# CPU.net
KiCad netlist of a schematic drawn in Altium Designer
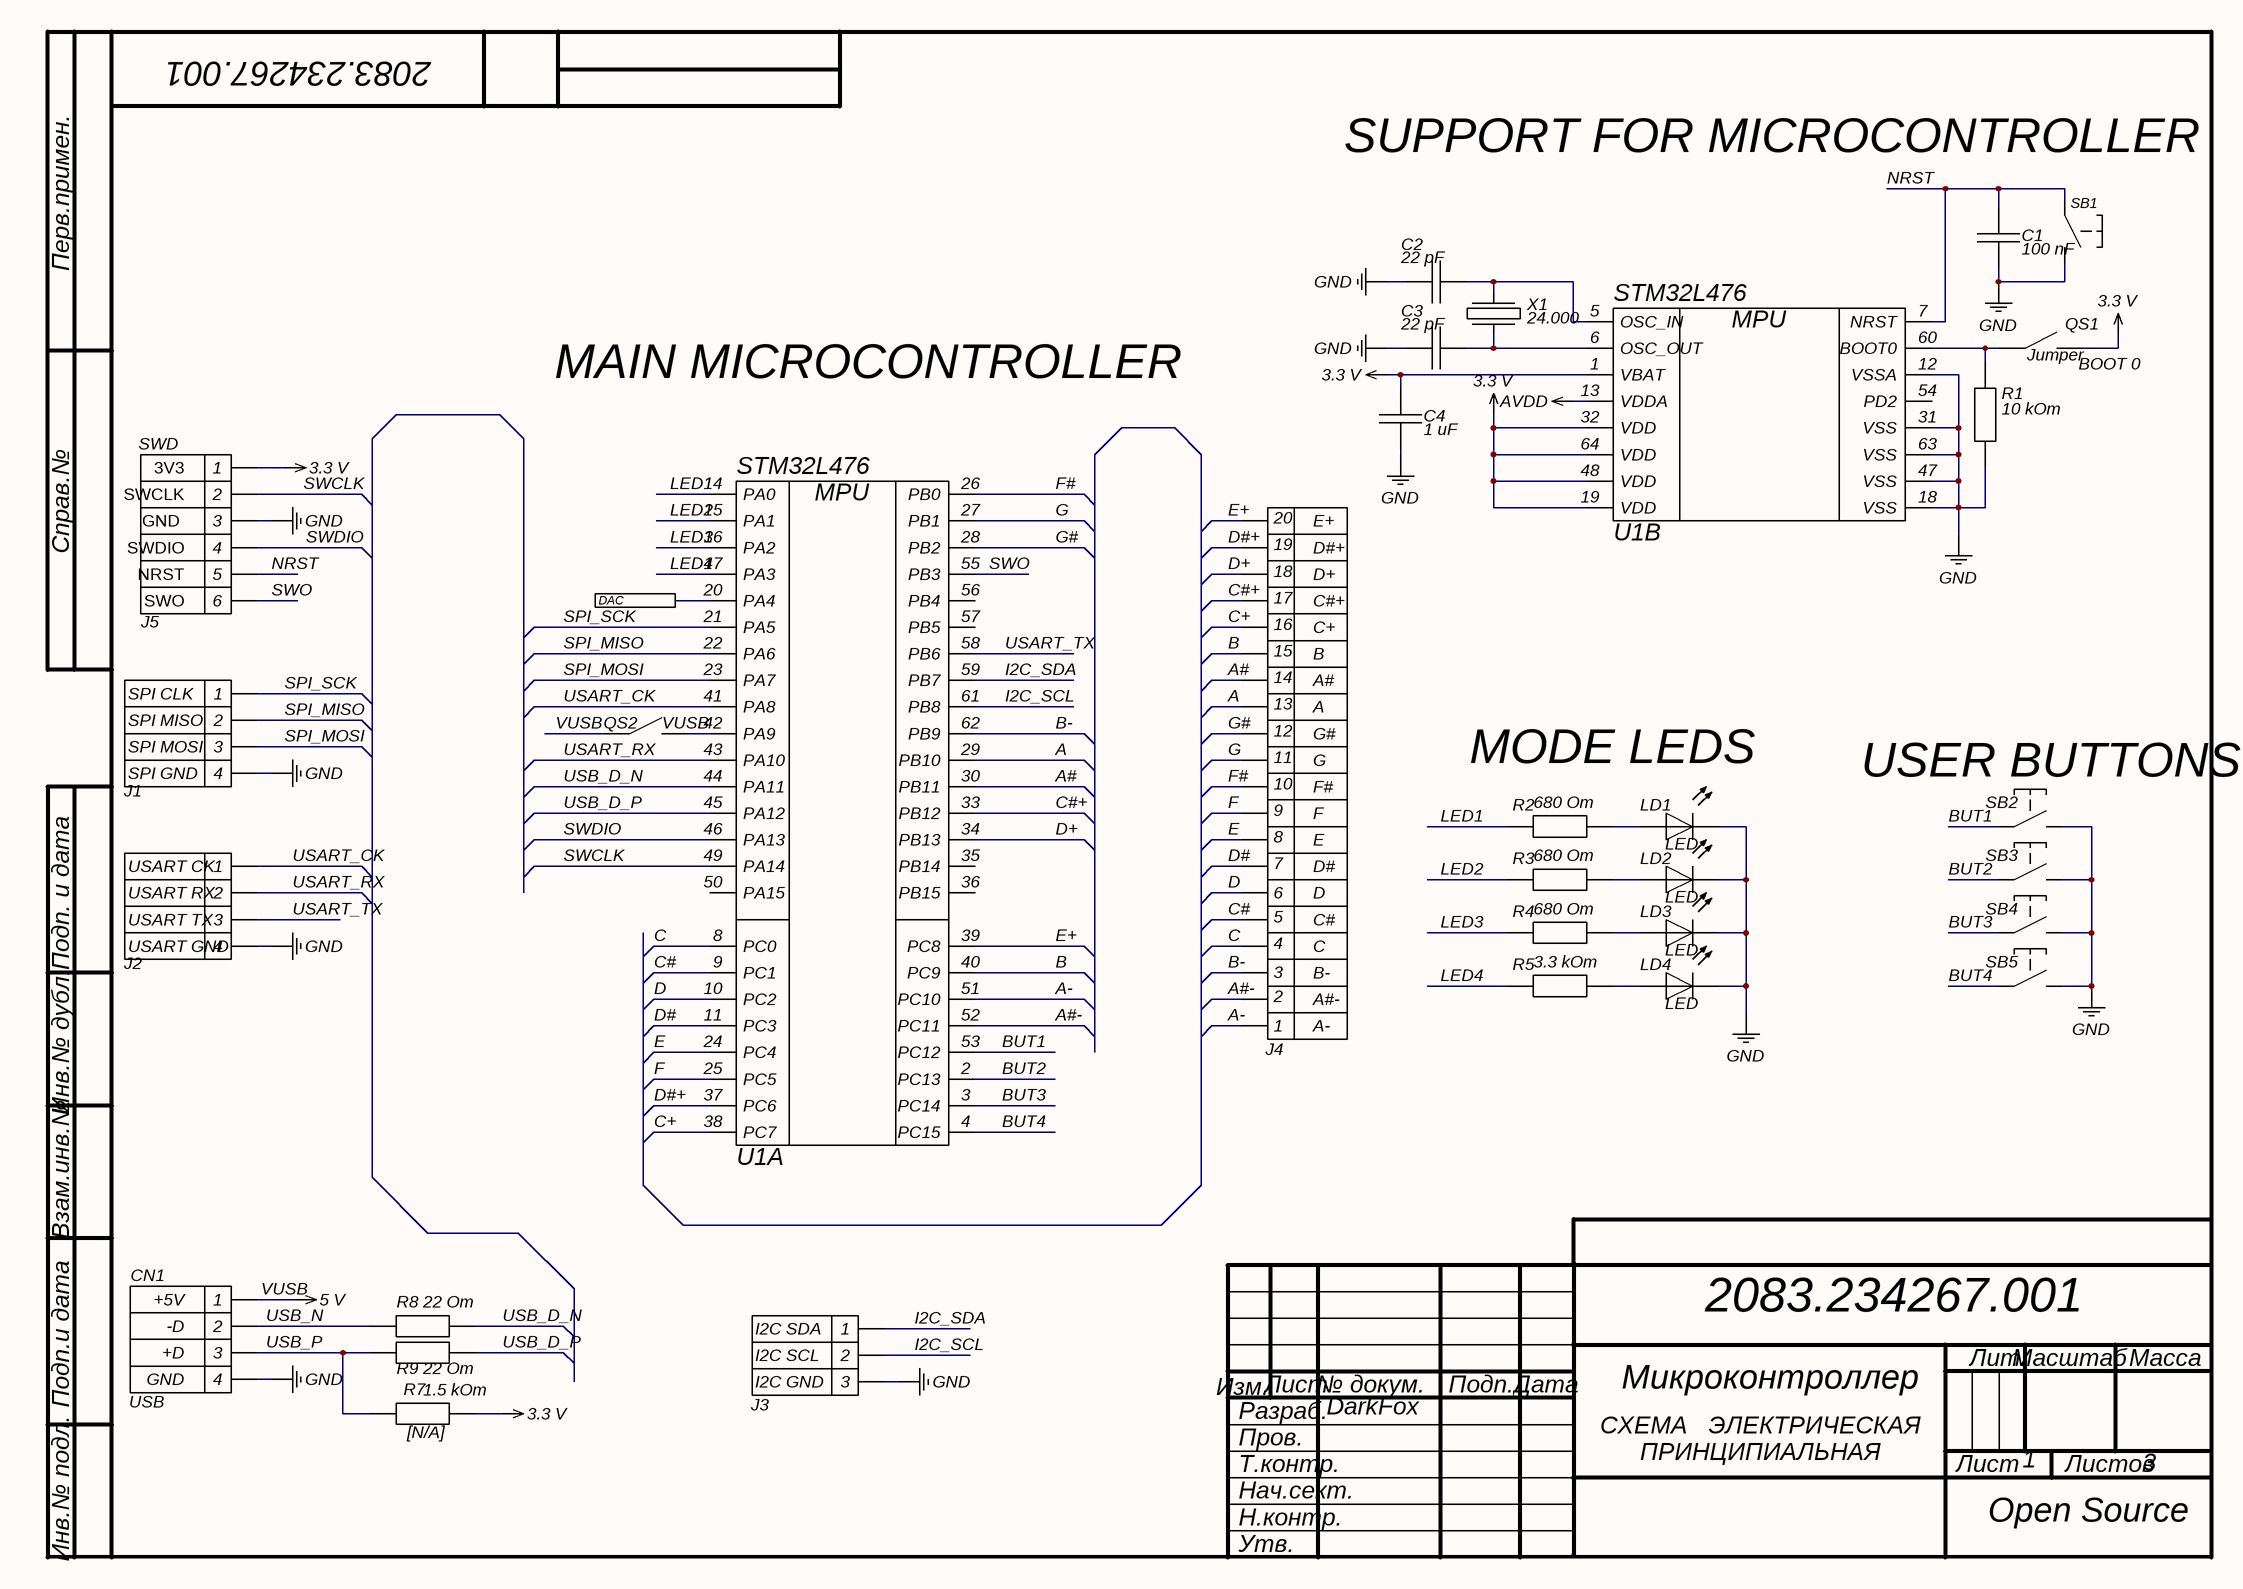
[diagram p0: CPU.SchDoc]

(export (version "E")
  (design (tool "Eeschema 10.0.6"))
  (components
    (comp (ref "C1") (value "100 nF") (footprint "0603") (libsource (lib "MyLib") (part "Cup")))
    (comp (ref "C2") (value "22 pF") (footprint "0805") (libsource (lib "MyLib") (part "Cup")))
    (comp (ref "C3") (value "22 pF") (footprint "0805") (libsource (lib "MyLib") (part "Cup")))
    (comp (ref "C4") (value "1 uF") (footprint "0603") (libsource (lib "MyLib") (part "Cup")))
    (comp (ref "CN1") (value "USB") (footprint "USB") (libsource (lib "ECard_Lib") (part "USB_2")))
    (comp (ref "J1") (value "4x2.54") (footprint "SMD 4x2.54") (libsource (lib "ECard_Lib") (part "4x2.54")))
    (comp (ref "J2") (value "4x2.54") (footprint "SMD 4x2.54") (libsource (lib "ECard_Lib") (part "4x2.54")))
    (comp (ref "J3") (value "3x2.54") (footprint "SMD 3x2.54") (libsource (lib "ECard_Lib") (part "3x2.54")))
    (comp (ref "J4")
      (value "piano_full")
      (footprint "PIANO_FULL")
      (libsource (lib "ECard_Lib") (part "piano_full"))
    )
    (comp (ref "J5") (value "SWD") (footprint "SWD_6_2.54") (libsource (lib "ECard_Lib") (part "SWD")))
    (comp (ref "LD1") (value "LED") (footprint "0805") (libsource (lib "MyLib") (part "LED")))
    (comp (ref "LD2") (value "LED") (footprint "0805") (libsource (lib "MyLib") (part "LED")))
    (comp (ref "LD3") (value "LED") (footprint "0805") (libsource (lib "MyLib") (part "LED")))
    (comp (ref "LD4") (value "LED") (footprint "0805") (libsource (lib "MyLib") (part "LED")))
    (comp (ref "QS1") (value "Jumper") (footprint "SB") (libsource (lib "ECard_Lib") (part "Jumper")))
    (comp (ref "QS2") (value "Jumper") (footprint "SB") (libsource (lib "ECard_Lib") (part "Jumper")))
    (comp (ref "R1") (value "10 kOm") (footprint "0603") (libsource (lib "ECard_Lib") (part "Res")))
    (comp (ref "R2") (value "680 Om") (footprint "1206") (libsource (lib "MyLib") (part "Res")))
    (comp (ref "R3") (value "680 Om") (footprint "1206") (libsource (lib "MyLib") (part "Res")))
    (comp (ref "R4") (value "680 Om") (footprint "1206") (libsource (lib "MyLib") (part "Res")))
    (comp (ref "R5") (value "3.3 kOm") (footprint "1206") (libsource (lib "MyLib") (part "Res")))
    (comp (ref "R7") (value "1.5 kOm") (footprint "1206") (libsource (lib "MyLib") (part "Res")))
    (comp (ref "R8") (value "22 Om") (footprint "1206") (libsource (lib "MyLib") (part "Res")))
    (comp (ref "R9") (value "22 Om") (footprint "1206") (libsource (lib "MyLib") (part "Res")))
    (comp (ref "SB1") (value "but") (footprint "TS44-SMD") (libsource (lib "ECard_Lib") (part "but")))
    (comp (ref "SB2") (value "but") (footprint "TS44-SMD") (libsource (lib "ECard_Lib") (part "but")))
    (comp (ref "SB3") (value "but") (footprint "TS44-SMD") (libsource (lib "ECard_Lib") (part "but")))
    (comp (ref "SB4") (value "but") (footprint "TS44-SMD") (libsource (lib "ECard_Lib") (part "but")))
    (comp (ref "SB5") (value "but") (footprint "TS44-SMD") (libsource (lib "ECard_Lib") (part "but")))
    (comp (ref "U1")
      (value "STM32L476")
      (footprint "LQFP - 64")
      (libsource (lib "ECard_Lib") (part "STM32L476RG"))
    )
    (comp (ref "X1")
      (value "24.000")
      (footprint "CSX-3225")
      (description "Crystal Resonator")
      (libsource (lib "MyLib") (part "CSX-3225"))
    )
  )
  (nets
    (net (code "1") (name "/A") (class "Default")
      (node (ref "J4") (pin "13") (pinfunction "A_13") (pintype "passive"))
      (node (ref "U1") (pin "29") (pinfunction "PB10_29") (pintype "passive"))
    )
    (net (code "2") (name "/A#") (class "Default")
      (node (ref "J4") (pin "14") (pinfunction "A#_14") (pintype "passive"))
      (node (ref "U1") (pin "30") (pinfunction "PB11_30") (pintype "passive"))
    )
    (net (code "3") (name "/A#-") (class "Default")
      (node (ref "J4") (pin "2") (pinfunction "A#-_2") (pintype "passive"))
      (node (ref "U1") (pin "52") (pinfunction "PC11_52") (pintype "passive"))
    )
    (net (code "4") (name "/A-") (class "Default")
      (node (ref "J4") (pin "1") (pinfunction "A-_1") (pintype "passive"))
      (node (ref "U1") (pin "51") (pinfunction "PC10_51") (pintype "passive"))
    )
    (net (code "5") (name "/B") (class "Default")
      (node (ref "J4") (pin "15") (pinfunction "B_15") (pintype "passive"))
      (node (ref "U1") (pin "40") (pinfunction "PC9_40") (pintype "passive"))
    )
    (net (code "6") (name "/B-") (class "Default")
      (node (ref "J4") (pin "3") (pinfunction "B-_3") (pintype "passive"))
      (node (ref "U1") (pin "62") (pinfunction "PB9_62") (pintype "passive"))
    )
    (net (code "7") (name "/BUT1") (class "Default")
      (node (ref "SB2") (pin "1") (pinfunction "1_1") (pintype "passive"))
      (node (ref "U1") (pin "53") (pinfunction "PC12_53") (pintype "passive"))
    )
    (net (code "8") (name "/BUT2") (class "Default")
      (node (ref "SB3") (pin "1") (pinfunction "1_1") (pintype "passive"))
      (node (ref "U1") (pin "2") (pinfunction "PC13_2") (pintype "passive"))
    )
    (net (code "9") (name "/BUT3") (class "Default")
      (node (ref "SB4") (pin "1") (pinfunction "1_1") (pintype "passive"))
      (node (ref "U1") (pin "3") (pinfunction "PC14_3") (pintype "passive"))
    )
    (net (code "10") (name "/BUT4") (class "Default")
      (node (ref "SB5") (pin "1") (pinfunction "1_1") (pintype "passive"))
      (node (ref "U1") (pin "4") (pinfunction "PC15_4") (pintype "passive"))
    )
    (net (code "11") (name "/C") (class "Default")
      (node (ref "J4") (pin "4") (pinfunction "C_4") (pintype "passive"))
      (node (ref "U1") (pin "8") (pinfunction "PC0_8") (pintype "passive"))
    )
    (net (code "12") (name "/C#") (class "Default")
      (node (ref "J4") (pin "5") (pinfunction "C#_5") (pintype "passive"))
      (node (ref "U1") (pin "9") (pinfunction "PC1_9") (pintype "passive"))
    )
    (net (code "13") (name "/C#+") (class "Default")
      (node (ref "J4") (pin "17") (pinfunction "C#+_17") (pintype "passive"))
      (node (ref "U1") (pin "33") (pinfunction "PB12_33") (pintype "passive"))
    )
    (net (code "14") (name "/C+") (class "Default")
      (node (ref "J4") (pin "16") (pinfunction "C+_16") (pintype "passive"))
      (node (ref "U1") (pin "38") (pinfunction "PC7_38") (pintype "passive"))
    )
    (net (code "15") (name "/D") (class "Default")
      (node (ref "J4") (pin "6") (pinfunction "D_6") (pintype "passive"))
      (node (ref "U1") (pin "10") (pinfunction "PC2_10") (pintype "passive"))
    )
    (net (code "16") (name "/D#") (class "Default")
      (node (ref "J4") (pin "7") (pinfunction "D#_7") (pintype "passive"))
      (node (ref "U1") (pin "11") (pinfunction "PC3_11") (pintype "passive"))
    )
    (net (code "17") (name "/D#+") (class "Default")
      (node (ref "J4") (pin "19") (pinfunction "D#+_19") (pintype "passive"))
      (node (ref "U1") (pin "37") (pinfunction "PC6_37") (pintype "passive"))
    )
    (net (code "18") (name "/D+") (class "Default")
      (node (ref "J4") (pin "18") (pinfunction "D+_18") (pintype "passive"))
      (node (ref "U1") (pin "34") (pinfunction "PB13_34") (pintype "passive"))
    )
    (net (code "19") (name "/DAC") (class "Default")
      (node (ref "U1") (pin "20") (pinfunction "PA4_20") (pintype "passive"))
    )
    (net (code "20") (name "/E") (class "Default")
      (node (ref "J4") (pin "8") (pinfunction "E_8") (pintype "passive"))
      (node (ref "U1") (pin "24") (pinfunction "PC4_24") (pintype "passive"))
    )
    (net (code "21") (name "/E+") (class "Default")
      (node (ref "J4") (pin "20") (pinfunction "E+_20") (pintype "passive"))
      (node (ref "U1") (pin "39") (pinfunction "PC8_39") (pintype "passive"))
    )
    (net (code "22") (name "/F") (class "Default")
      (node (ref "J4") (pin "9") (pinfunction "F_9") (pintype "passive"))
      (node (ref "U1") (pin "25") (pinfunction "PC5_25") (pintype "passive"))
    )
    (net (code "23") (name "/F#") (class "Default")
      (node (ref "J4") (pin "10") (pinfunction "F#_10") (pintype "passive"))
      (node (ref "U1") (pin "26") (pinfunction "PB0_26") (pintype "passive"))
    )
    (net (code "24") (name "/G") (class "Default")
      (node (ref "J4") (pin "11") (pinfunction "G_11") (pintype "passive"))
      (node (ref "U1") (pin "27") (pinfunction "PB1_27") (pintype "passive"))
    )
    (net (code "25") (name "/G#") (class "Default")
      (node (ref "J4") (pin "12") (pinfunction "G#_12") (pintype "passive"))
      (node (ref "U1") (pin "28") (pinfunction "PB2_28") (pintype "passive"))
    )
    (net (code "26") (name "/I2C_SCL") (class "Default")
      (node (ref "J3") (pin "2") (pinfunction "2_2") (pintype "passive"))
      (node (ref "U1") (pin "61") (pinfunction "PB8_61") (pintype "passive"))
    )
    (net (code "27") (name "/I2C_SDA") (class "Default")
      (node (ref "J3") (pin "1") (pinfunction "1_1") (pintype "passive"))
      (node (ref "U1") (pin "59") (pinfunction "PB7_59") (pintype "passive"))
    )
    (net (code "28") (name "/LED1") (class "Default")
      (node (ref "R2") (pin "1") (pinfunction "1_1") (pintype "passive"))
      (node (ref "U1") (pin "14") (pinfunction "PA0_14") (pintype "passive"))
    )
    (net (code "29") (name "/LED2") (class "Default")
      (node (ref "R3") (pin "1") (pinfunction "1_1") (pintype "passive"))
      (node (ref "U1") (pin "15") (pinfunction "PA1_15") (pintype "passive"))
    )
    (net (code "30") (name "/LED3") (class "Default")
      (node (ref "R4") (pin "1") (pinfunction "1_1") (pintype "passive"))
      (node (ref "U1") (pin "16") (pinfunction "PA2_16") (pintype "passive"))
    )
    (net (code "31") (name "/LED4") (class "Default")
      (node (ref "R5") (pin "1") (pinfunction "1_1") (pintype "passive"))
      (node (ref "U1") (pin "17") (pinfunction "PA3_17") (pintype "passive"))
    )
    (net (code "32") (name "/NRST") (class "Default")
      (node (ref "C1") (pin "2") (pinfunction "2_2") (pintype "passive"))
      (node (ref "J5") (pin "5") (pinfunction "NRST_5") (pintype "passive"))
      (node (ref "SB1") (pin "1") (pinfunction "1_1") (pintype "passive"))
      (node (ref "U1") (pin "7") (pinfunction "NRST_7") (pintype "passive"))
    )
    (net (code "33") (name "/SPI_MISO") (class "Default")
      (node (ref "J1") (pin "2") (pinfunction "2_2") (pintype "passive"))
      (node (ref "U1") (pin "22") (pinfunction "PA6_22") (pintype "passive"))
    )
    (net (code "34") (name "/SPI_MOSI") (class "Default")
      (node (ref "J1") (pin "3") (pinfunction "3_3") (pintype "passive"))
      (node (ref "U1") (pin "23") (pinfunction "PA7_23") (pintype "passive"))
    )
    (net (code "35") (name "/SPI_SCK") (class "Default")
      (node (ref "J1") (pin "1") (pinfunction "1_1") (pintype "passive"))
      (node (ref "U1") (pin "21") (pinfunction "PA5_21") (pintype "passive"))
    )
    (net (code "36") (name "/SWCLK") (class "Default")
      (node (ref "J5") (pin "2") (pinfunction "SWCLK_2") (pintype "passive"))
      (node (ref "U1") (pin "49") (pinfunction "PA14_49") (pintype "passive"))
    )
    (net (code "37") (name "/SWDIO") (class "Default")
      (node (ref "J5") (pin "4") (pinfunction "SWDIO_4") (pintype "passive"))
      (node (ref "U1") (pin "46") (pinfunction "PA13_46") (pintype "passive"))
    )
    (net (code "38") (name "/SWO") (class "Default")
      (node (ref "J5") (pin "6") (pinfunction "SWO_6") (pintype "passive"))
      (node (ref "U1") (pin "55") (pinfunction "PB3_55") (pintype "passive"))
    )
    (net (code "39") (name "/USART_CK") (class "Default")
      (node (ref "J2") (pin "1") (pinfunction "1_1") (pintype "passive"))
      (node (ref "U1") (pin "41") (pinfunction "PA8_41") (pintype "passive"))
    )
    (net (code "40") (name "/USART_RX") (class "Default")
      (node (ref "J2") (pin "2") (pinfunction "2_2") (pintype "passive"))
      (node (ref "U1") (pin "43") (pinfunction "PA10_43") (pintype "passive"))
    )
    (net (code "41") (name "/USART_TX") (class "Default")
      (node (ref "J2") (pin "3") (pinfunction "3_3") (pintype "passive"))
      (node (ref "U1") (pin "58") (pinfunction "PB6_58") (pintype "passive"))
    )
    (net (code "42") (name "/USB_D_N") (class "Default")
      (node (ref "R8") (pin "2") (pinfunction "2_2") (pintype "passive"))
      (node (ref "U1") (pin "44") (pinfunction "PA11_44") (pintype "passive"))
    )
    (net (code "43") (name "/USB_D_P") (class "Default")
      (node (ref "R9") (pin "2") (pinfunction "2_2") (pintype "passive"))
      (node (ref "U1") (pin "45") (pinfunction "PA12_45") (pintype "passive"))
    )
    (net (code "44") (name "/USB_N") (class "Default")
      (node (ref "CN1") (pin "2") (pinfunction "-D_2") (pintype "passive"))
      (node (ref "R8") (pin "1") (pinfunction "1_1") (pintype "passive"))
    )
    (net (code "45") (name "/USB_P") (class "Default")
      (node (ref "CN1") (pin "3") (pinfunction "+D_3") (pintype "passive"))
      (node (ref "R7") (pin "1") (pinfunction "1_1") (pintype "passive"))
      (node (ref "R9") (pin "1") (pinfunction "1_1") (pintype "passive"))
    )
    (net (code "46") (name "3.3 V") (class "Default")
      (node (ref "C4") (pin "2") (pinfunction "2_2") (pintype "passive"))
      (node (ref "J5") (pin "1") (pinfunction "3V3_1") (pintype "passive"))
      (node (ref "QS1") (pin "2") (pinfunction "2_2") (pintype "passive"))
      (node (ref "R7") (pin "2") (pinfunction "2_2") (pintype "passive"))
      (node (ref "U1") (pin "1") (pinfunction "VBAT_1") (pintype "passive"))
      (node (ref "U1") (pin "19") (pinfunction "VDD_19") (pintype "passive"))
      (node (ref "U1") (pin "32") (pinfunction "VDD_32") (pintype "passive"))
      (node (ref "U1") (pin "48") (pinfunction "VDD_48") (pintype "passive"))
      (node (ref "U1") (pin "64") (pinfunction "VDD_64") (pintype "passive"))
    )
    (net (code "47") (name "5 V") (class "Default")
      (node (ref "CN1") (pin "1") (pinfunction "+5V_1") (pintype "power_in"))
      (node (ref "QS2") (pin "1") (pinfunction "1_1") (pintype "passive"))
    )
    (net (code "48") (name "AVDD") (class "Default")
      (node (ref "U1") (pin "13") (pinfunction "VDDA_13") (pintype "passive"))
    )
    (net (code "49") (name "GND") (class "Default")
      (node (ref "C1") (pin "1") (pinfunction "1_1") (pintype "passive"))
      (node (ref "C2") (pin "1") (pinfunction "1_1") (pintype "passive"))
      (node (ref "C3") (pin "1") (pinfunction "1_1") (pintype "passive"))
      (node (ref "C4") (pin "1") (pinfunction "1_1") (pintype "passive"))
      (node (ref "CN1") (pin "4") (pinfunction "GND_4") (pintype "passive"))
      (node (ref "J1") (pin "4") (pinfunction "4_4") (pintype "passive"))
      (node (ref "J2") (pin "4") (pinfunction "4_4") (pintype "passive"))
      (node (ref "J3") (pin "3") (pinfunction "3_3") (pintype "passive"))
      (node (ref "J5") (pin "3") (pinfunction "GND_3") (pintype "passive"))
      (node (ref "LD1") (pin "2") (pinfunction "2_2") (pintype "passive"))
      (node (ref "LD2") (pin "2") (pinfunction "2_2") (pintype "passive"))
      (node (ref "LD3") (pin "2") (pinfunction "2_2") (pintype "passive"))
      (node (ref "LD4") (pin "2") (pinfunction "2_2") (pintype "passive"))
      (node (ref "R1") (pin "1") (pinfunction "1_1") (pintype "passive"))
      (node (ref "SB1") (pin "2") (pinfunction "2_2") (pintype "passive"))
      (node (ref "SB2") (pin "2") (pinfunction "2_2") (pintype "passive"))
      (node (ref "SB3") (pin "2") (pinfunction "2_2") (pintype "passive"))
      (node (ref "SB4") (pin "2") (pinfunction "2_2") (pintype "passive"))
      (node (ref "SB5") (pin "2") (pinfunction "2_2") (pintype "passive"))
      (node (ref "U1") (pin "12") (pinfunction "VSSA_12") (pintype "passive"))
      (node (ref "U1") (pin "18") (pinfunction "VSS_18") (pintype "passive"))
      (node (ref "U1") (pin "31") (pinfunction "VSS_31") (pintype "passive"))
      (node (ref "U1") (pin "47") (pinfunction "VSS_47") (pintype "passive"))
      (node (ref "U1") (pin "63") (pinfunction "VSS_63") (pintype "passive"))
    )
    (net (code "50") (name "Net-(LD1-2-Pad1)") (class "Default")
      (node (ref "LD1") (pin "1") (pinfunction "2_1") (pintype "passive"))
      (node (ref "R2") (pin "2") (pinfunction "2_2") (pintype "passive"))
    )
    (net (code "51") (name "Net-(LD2-2-Pad1)") (class "Default")
      (node (ref "LD2") (pin "1") (pinfunction "2_1") (pintype "passive"))
      (node (ref "R3") (pin "2") (pinfunction "2_2") (pintype "passive"))
    )
    (net (code "52") (name "Net-(LD3-2-Pad1)") (class "Default")
      (node (ref "LD3") (pin "1") (pinfunction "2_1") (pintype "passive"))
      (node (ref "R4") (pin "2") (pinfunction "2_2") (pintype "passive"))
    )
    (net (code "53") (name "Net-(LD4-2-Pad1)") (class "Default")
      (node (ref "LD4") (pin "1") (pinfunction "2_1") (pintype "passive"))
      (node (ref "R5") (pin "2") (pinfunction "2_2") (pintype "passive"))
    )
    (net (code "54") (name "Net-(U1A-PA9)") (class "Default")
      (node (ref "QS2") (pin "2") (pinfunction "2_2") (pintype "passive"))
      (node (ref "U1") (pin "42") (pinfunction "PA9_42") (pintype "passive"))
    )
    (net (code "55") (name "Net-(U1B-BOOT0)") (class "Default")
      (node (ref "QS1") (pin "1") (pinfunction "1_1") (pintype "passive"))
      (node (ref "R1") (pin "2") (pinfunction "2_2") (pintype "passive"))
      (node (ref "U1") (pin "60") (pinfunction "BOOT0_60") (pintype "passive"))
    )
    (net (code "56") (name "Net-(U1B-OSC_IN)") (class "Default")
      (node (ref "C2") (pin "2") (pinfunction "2_2") (pintype "passive"))
      (node (ref "U1") (pin "5") (pinfunction "OSC_IN_5") (pintype "passive"))
      (node (ref "X1") (pin "2") (pinfunction "2_2") (pintype "passive"))
    )
    (net (code "57") (name "Net-(U1B-OSC_OUT)") (class "Default")
      (node (ref "C3") (pin "2") (pinfunction "2_2") (pintype "passive"))
      (node (ref "U1") (pin "6") (pinfunction "OSC_OUT_6") (pintype "passive"))
      (node (ref "X1") (pin "1") (pinfunction "1_1") (pintype "passive"))
    )
    (net (code "58") (name "unconnected-(U1A-PA15-Pad50)") (class "Default")
      (node (ref "U1") (pin "50") (pinfunction "PA15_50") (pintype "passive"))
    )
    (net (code "59") (name "unconnected-(U1A-PB4-Pad56)") (class "Default")
      (node (ref "U1") (pin "56") (pinfunction "PB4_56") (pintype "passive"))
    )
    (net (code "60") (name "unconnected-(U1A-PB5-Pad57)") (class "Default")
      (node (ref "U1") (pin "57") (pinfunction "PB5_57") (pintype "passive"))
    )
    (net (code "61") (name "unconnected-(U1A-PB14-Pad35)") (class "Default")
      (node (ref "U1") (pin "35") (pinfunction "PB14_35") (pintype "passive"))
    )
    (net (code "62") (name "unconnected-(U1A-PB15-Pad36)") (class "Default")
      (node (ref "U1") (pin "36") (pinfunction "PB15_36") (pintype "passive"))
    )
    (net (code "63") (name "unconnected-(U1B-PD2-Pad54)") (class "Default")
      (node (ref "U1") (pin "54") (pinfunction "PD2_54") (pintype "passive"))
    )
  )
)
